# io.net
KiCad netlist of a schematic drawn in Altium Designer
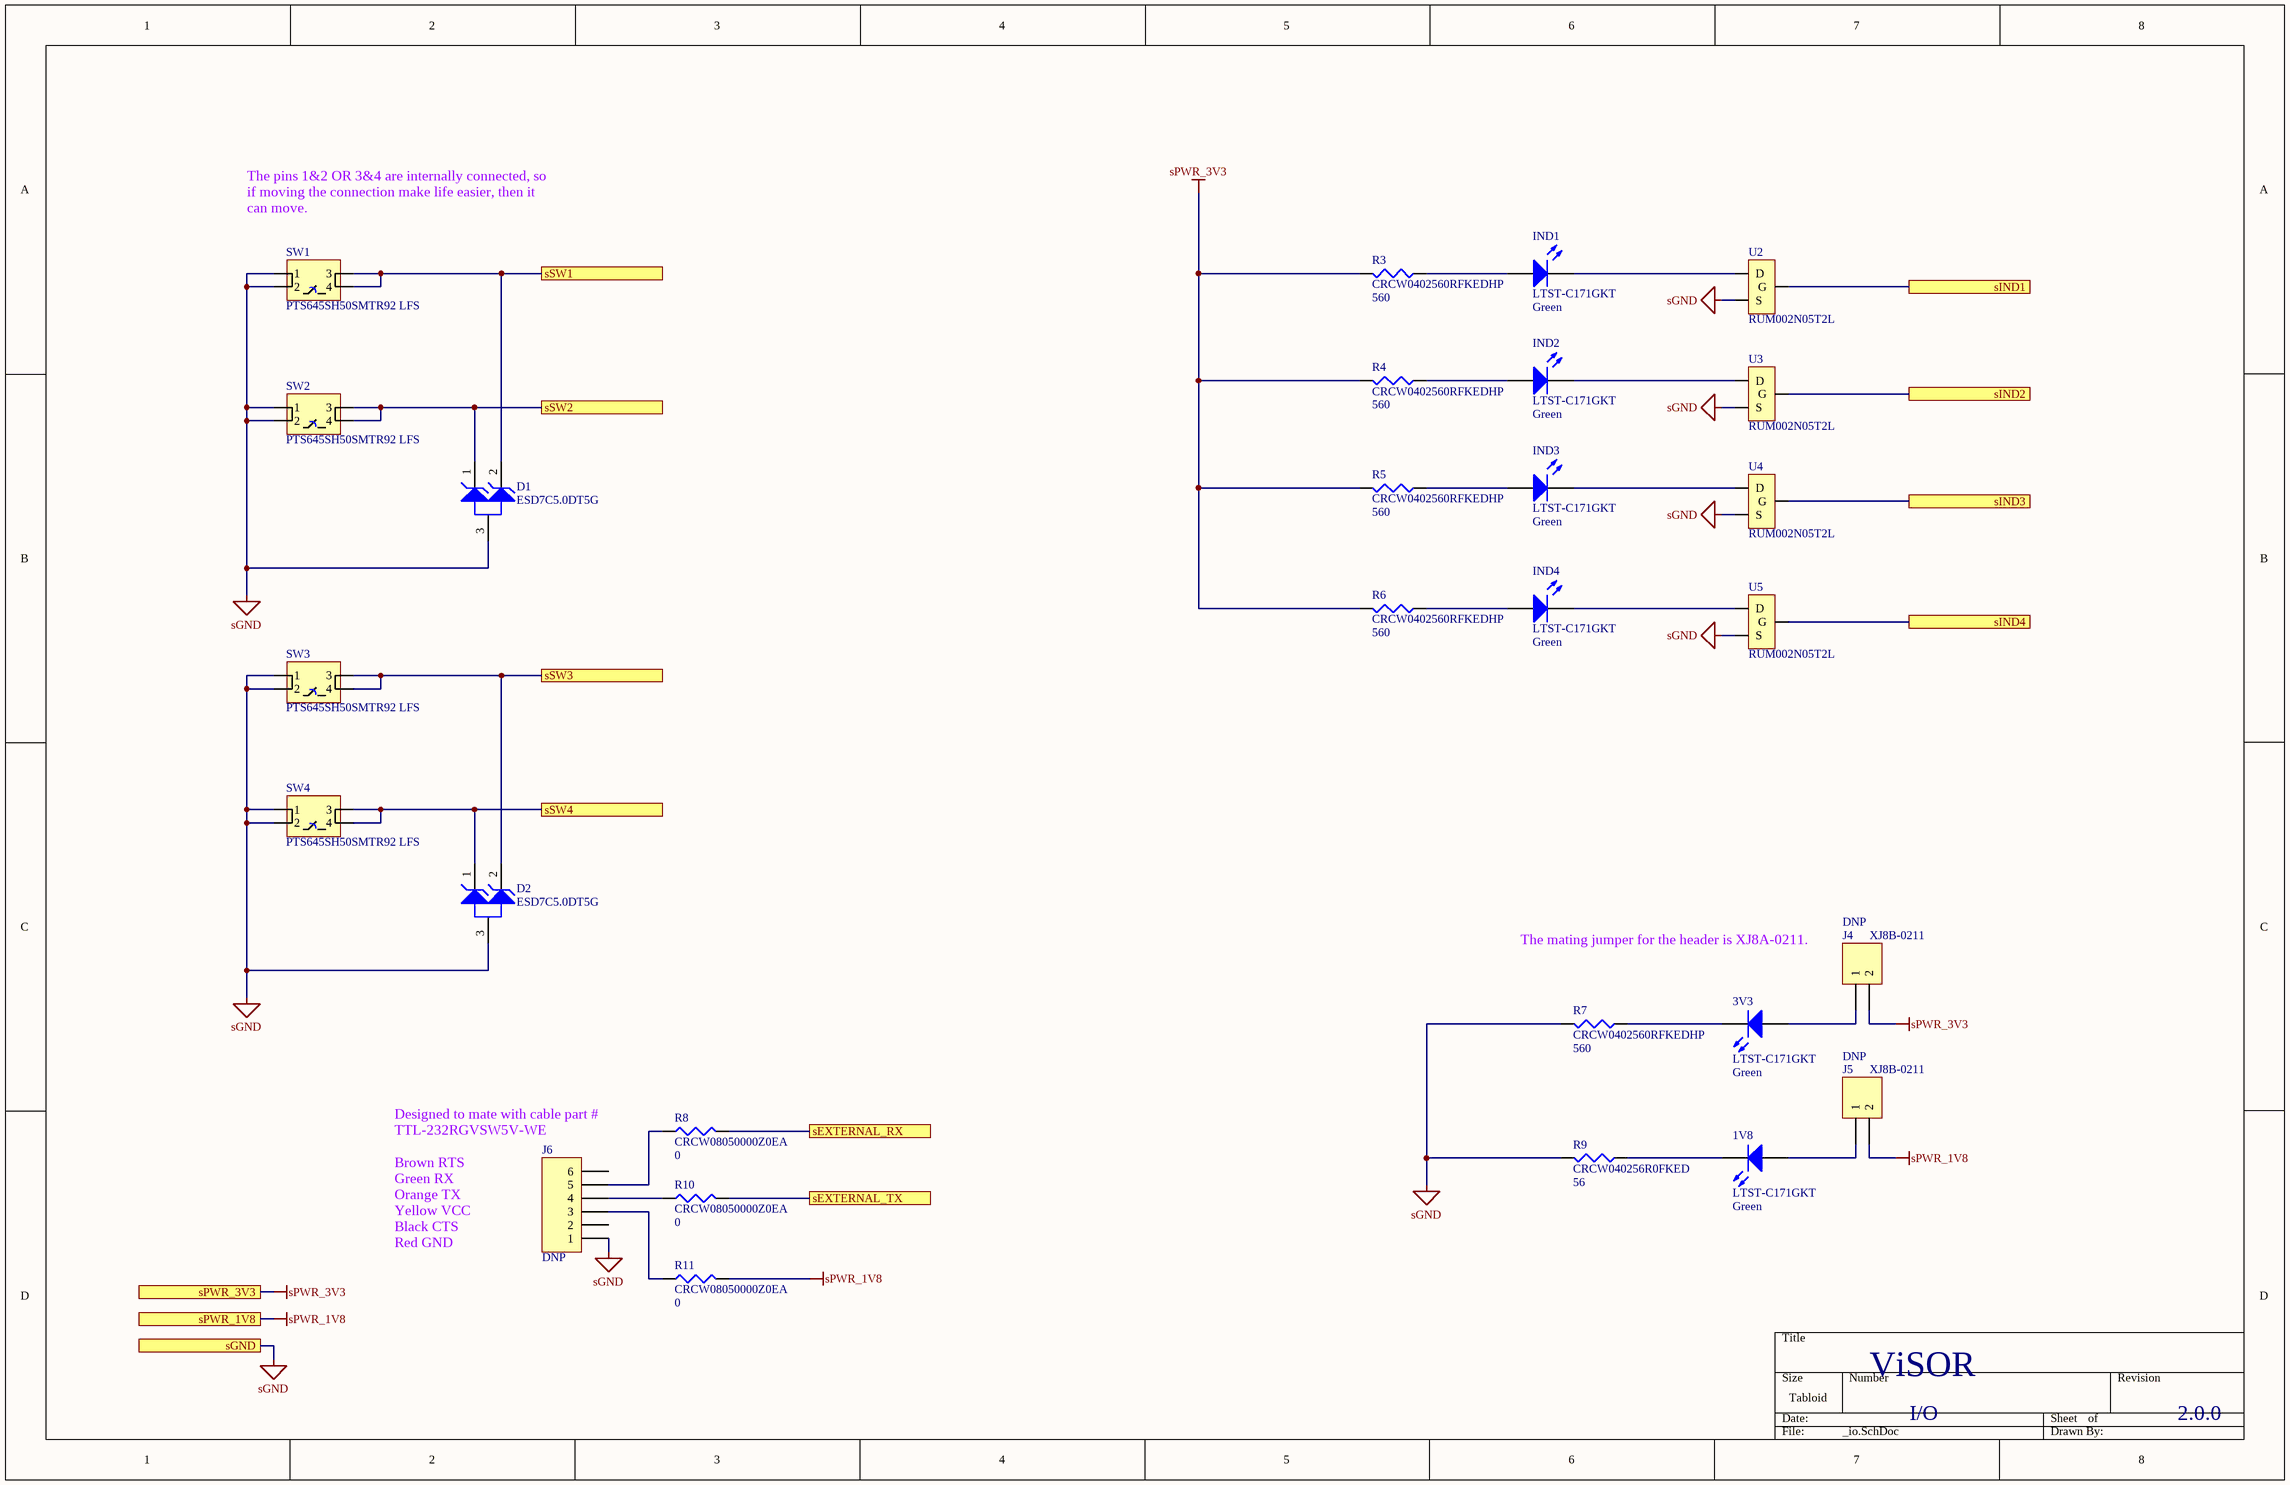
[diagram p0: _io.SchDoc]

(export (version "E")
  (design (tool "Eeschema 10.0.6"))
  (components
    (comp (ref "1V8")
      (value "LTST-C171GKT")
      (footprint "0805")
      (description "LED")
      (fields (field (name "COLOR") "Green"))
      (libsource (lib "lite-on") (part "LTST-C171GKT"))
    )
    (comp (ref "3V3")
      (value "LTST-C171GKT")
      (footprint "0805")
      (description "LED")
      (fields (field (name "COLOR") "Green"))
      (libsource (lib "lite-on") (part "LTST-C171GKT"))
    )
    (comp (ref "D1")
      (value "ESD7C5.0DT5G")
      (footprint "ONSC-SOT-723-3-631AA-01_V")
      (fields (field (name "MANUFACTURER") "On Semiconductor"))
      (libsource (lib "Altium Content Vault") (part "ONSC-K1K2A3-3"))
    )
    (comp (ref "D2")
      (value "ESD7C5.0DT5G")
      (footprint "ONSC-SOT-723-3-631AA-01_V")
      (fields (field (name "MANUFACTURER") "On Semiconductor"))
      (libsource (lib "Altium Content Vault") (part "ONSC-K1K2A3-3"))
    )
    (comp (ref "IND1")
      (value "LTST-C171GKT")
      (footprint "0805")
      (description "LED")
      (fields (field (name "COLOR") "Green"))
      (libsource (lib "lite-on") (part "LTST-C171GKT"))
    )
    (comp (ref "IND2")
      (value "LTST-C171GKT")
      (footprint "0805")
      (description "LED")
      (fields (field (name "COLOR") "Green"))
      (libsource (lib "lite-on") (part "LTST-C171GKT"))
    )
    (comp (ref "IND3")
      (value "LTST-C171GKT")
      (footprint "0805")
      (description "LED")
      (fields (field (name "COLOR") "Green"))
      (libsource (lib "lite-on") (part "LTST-C171GKT"))
    )
    (comp (ref "IND4")
      (value "LTST-C171GKT")
      (footprint "0805")
      (description "LED")
      (fields (field (name "COLOR") "Green"))
      (libsource (lib "lite-on") (part "LTST-C171GKT"))
    )
    (comp (ref "J4")
      (value "XJ8B-0211")
      (footprint "HDR1X2")
      (description "Header, 2-Pin")
      (fields (field (name "DNP") "DNP") (field (name "PUBLISHER") "Altium Limited"))
      (libsource (lib "Miscellaneous Connectors") (part "Header 2"))
    )
    (comp (ref "J5")
      (value "XJ8B-0211")
      (footprint "HDR1X2")
      (description "Header, 2-Pin")
      (fields (field (name "DNP") "DNP") (field (name "PUBLISHER") "Altium Limited"))
      (libsource (lib "Miscellaneous Connectors") (part "Header 2"))
    )
    (comp (ref "J6")
      (value "DNP")
      (footprint "HDR1X6")
      (description "Header, 6-Pin")
      (fields (field (name "PUBLISHER") "Altium Limited"))
      (libsource (lib "miscellaneous_connectors") (part "Header 6"))
    )
    (comp (ref "R3")
      (value "CRCW0402560RFKEDHP")
      (footprint "0402")
      (description "0.125W, -55-155C, 1005, 50V, ±1%")
      (fields (field (name "ALTIUM_VALUE") "560"))
      (libsource (lib "standard_resistors") (part "CRCW0402xxxxFKED"))
    )
    (comp (ref "R4")
      (value "CRCW0402560RFKEDHP")
      (footprint "0402")
      (description "0.125W, -55-155C, 1005, 50V, ±1%")
      (fields (field (name "ALTIUM_VALUE") "560"))
      (libsource (lib "standard_resistors") (part "CRCW0402xxxxFKED"))
    )
    (comp (ref "R5")
      (value "CRCW0402560RFKEDHP")
      (footprint "0402")
      (description "0.125W, -55-155C, 1005, 50V, ±1%")
      (fields (field (name "ALTIUM_VALUE") "560"))
      (libsource (lib "standard_resistors") (part "CRCW0402xxxxFKED"))
    )
    (comp (ref "R6")
      (value "CRCW0402560RFKEDHP")
      (footprint "0402")
      (description "0.125W, -55-155C, 1005, 50V, ±1%")
      (fields (field (name "ALTIUM_VALUE") "560"))
      (libsource (lib "standard_resistors") (part "CRCW0402xxxxFKED"))
    )
    (comp (ref "R7")
      (value "CRCW0402560RFKEDHP")
      (footprint "0402")
      (description "0.125W, -55-155C, 1005, 50V, ±1%")
      (fields (field (name "ALTIUM_VALUE") "560"))
      (libsource (lib "standard_resistors") (part "CRCW0402xxxxFKED"))
    )
    (comp (ref "R8")
      (value "CRCW08050000Z0EA")
      (footprint "6-0805_M")
      (description "0Ω Resistor")
      (fields (field (name "ALTIUM_VALUE") "0") (field (name "PUBLISHER") "Altium Limited"))
      (libsource (lib "miscellaneous_devices") (part "Res3"))
    )
    (comp (ref "R9")
      (value "CRCW040256R0FKED")
      (footprint "0402")
      (description "0.125W, -55-155C, 1005, 50V, ±1%")
      (fields (field (name "ALTIUM_VALUE") "56"))
      (libsource (lib "standard_resistors") (part "CRCW0402xxxxFKED"))
    )
    (comp (ref "R10")
      (value "CRCW08050000Z0EA")
      (footprint "6-0805_M")
      (description "0Ω Resistor")
      (fields (field (name "ALTIUM_VALUE") "0") (field (name "PUBLISHER") "Altium Limited"))
      (libsource (lib "miscellaneous_devices") (part "Res3"))
    )
    (comp (ref "R11")
      (value "CRCW08050000Z0EA")
      (footprint "6-0805_M")
      (description "0Ω Resistor")
      (fields (field (name "ALTIUM_VALUE") "0") (field (name "PUBLISHER") "Altium Limited"))
      (libsource (lib "miscellaneous_devices") (part "Res3"))
    )
    (comp (ref "SW1")
      (value "PTS645SH50SMTR92 LFS")
      (footprint "PTS645SH50SMTR92 LFS")
      (description "Tactile Switch")
      (libsource (lib "candk") (part "PTS645SH50SMTR92 LFS"))
    )
    (comp (ref "SW2")
      (value "PTS645SH50SMTR92 LFS")
      (footprint "PTS645SH50SMTR92 LFS")
      (description "Tactile Switch")
      (libsource (lib "candk") (part "PTS645SH50SMTR92 LFS"))
    )
    (comp (ref "SW3")
      (value "PTS645SH50SMTR92 LFS")
      (footprint "PTS645SH50SMTR92 LFS")
      (description "Tactile Switch")
      (libsource (lib "candk") (part "PTS645SH50SMTR92 LFS"))
    )
    (comp (ref "SW4")
      (value "PTS645SH50SMTR92 LFS")
      (footprint "PTS645SH50SMTR92 LFS")
      (description "Tactile Switch")
      (libsource (lib "candk") (part "PTS645SH50SMTR92 LFS"))
    )
    (comp (ref "U2")
      (value "RUM002N05T2L")
      (footprint "RUM002N05T2L")
      (description "MOSFET N-CH 50V 0.2A 3VMT")
      (libsource (lib "rohm") (part "RUM002N05T2L"))
    )
    (comp (ref "U3")
      (value "RUM002N05T2L")
      (footprint "RUM002N05T2L")
      (description "MOSFET N-CH 50V 0.2A 3VMT")
      (libsource (lib "rohm") (part "RUM002N05T2L"))
    )
    (comp (ref "U4")
      (value "RUM002N05T2L")
      (footprint "RUM002N05T2L")
      (description "MOSFET N-CH 50V 0.2A 3VMT")
      (libsource (lib "rohm") (part "RUM002N05T2L"))
    )
    (comp (ref "U5")
      (value "RUM002N05T2L")
      (footprint "RUM002N05T2L")
      (description "MOSFET N-CH 50V 0.2A 3VMT")
      (libsource (lib "rohm") (part "RUM002N05T2L"))
    )
  )
  (nets
    (net (code "1") (name "/sEXTERNAL_RX") (class "Default")
      (node (ref "R8") (pin "2") (pinfunction "2_2") (pintype "passive"))
    )
    (net (code "2") (name "/sEXTERNAL_TX") (class "Default")
      (node (ref "R10") (pin "2") (pinfunction "2_2") (pintype "passive"))
    )
    (net (code "3") (name "/sIND1") (class "Default")
      (node (ref "U2") (pin "1") (pinfunction "G_1") (pintype "passive"))
    )
    (net (code "4") (name "/sIND2") (class "Default")
      (node (ref "U3") (pin "1") (pinfunction "G_1") (pintype "passive"))
    )
    (net (code "5") (name "/sIND3") (class "Default")
      (node (ref "U4") (pin "1") (pinfunction "G_1") (pintype "passive"))
    )
    (net (code "6") (name "/sIND4") (class "Default")
      (node (ref "U5") (pin "1") (pinfunction "G_1") (pintype "passive"))
    )
    (net (code "7") (name "/sSW1") (class "Default")
      (node (ref "D1") (pin "2") (pinfunction "K2_2") (pintype "passive"))
      (node (ref "SW1") (pin "3") (pinfunction "3_3") (pintype "passive"))
      (node (ref "SW1") (pin "4") (pinfunction "4_4") (pintype "passive"))
    )
    (net (code "8") (name "/sSW2") (class "Default")
      (node (ref "D1") (pin "1") (pinfunction "K1_1") (pintype "passive"))
      (node (ref "SW2") (pin "3") (pinfunction "3_3") (pintype "passive"))
      (node (ref "SW2") (pin "4") (pinfunction "4_4") (pintype "passive"))
    )
    (net (code "9") (name "/sSW3") (class "Default")
      (node (ref "D2") (pin "2") (pinfunction "K2_2") (pintype "passive"))
      (node (ref "SW3") (pin "3") (pinfunction "3_3") (pintype "passive"))
      (node (ref "SW3") (pin "4") (pinfunction "4_4") (pintype "passive"))
    )
    (net (code "10") (name "/sSW4") (class "Default")
      (node (ref "D2") (pin "1") (pinfunction "K1_1") (pintype "passive"))
      (node (ref "SW4") (pin "3") (pinfunction "3_3") (pintype "passive"))
      (node (ref "SW4") (pin "4") (pinfunction "4_4") (pintype "passive"))
    )
    (net (code "11") (name "Net-(1V8-A)") (class "Default")
      (node (ref "1V8") (pin "1") (pinfunction "A_1") (pintype "passive"))
      (node (ref "J5") (pin "1") (pinfunction "1_1") (pintype "passive"))
    )
    (net (code "12") (name "Net-(1V8-K)") (class "Default")
      (node (ref "1V8") (pin "2") (pinfunction "K_2") (pintype "passive"))
      (node (ref "R9") (pin "1") (pinfunction "1_1") (pintype "passive"))
    )
    (net (code "13") (name "Net-(3V3-A)") (class "Default")
      (node (ref "3V3") (pin "1") (pinfunction "A_1") (pintype "passive"))
      (node (ref "J4") (pin "1") (pinfunction "1_1") (pintype "passive"))
    )
    (net (code "14") (name "Net-(3V3-K)") (class "Default")
      (node (ref "3V3") (pin "2") (pinfunction "K_2") (pintype "passive"))
      (node (ref "R7") (pin "1") (pinfunction "1_1") (pintype "passive"))
    )
    (net (code "15") (name "Net-(IND1-A)") (class "Default")
      (node (ref "IND1") (pin "1") (pinfunction "A_1") (pintype "passive"))
      (node (ref "R3") (pin "1") (pinfunction "1_1") (pintype "passive"))
    )
    (net (code "16") (name "Net-(IND1-K)") (class "Default")
      (node (ref "IND1") (pin "2") (pinfunction "K_2") (pintype "passive"))
      (node (ref "U2") (pin "3") (pinfunction "D_3") (pintype "passive"))
    )
    (net (code "17") (name "Net-(IND2-A)") (class "Default")
      (node (ref "IND2") (pin "1") (pinfunction "A_1") (pintype "passive"))
      (node (ref "R4") (pin "1") (pinfunction "1_1") (pintype "passive"))
    )
    (net (code "18") (name "Net-(IND2-K)") (class "Default")
      (node (ref "IND2") (pin "2") (pinfunction "K_2") (pintype "passive"))
      (node (ref "U3") (pin "3") (pinfunction "D_3") (pintype "passive"))
    )
    (net (code "19") (name "Net-(IND3-A)") (class "Default")
      (node (ref "IND3") (pin "1") (pinfunction "A_1") (pintype "passive"))
      (node (ref "R5") (pin "1") (pinfunction "1_1") (pintype "passive"))
    )
    (net (code "20") (name "Net-(IND3-K)") (class "Default")
      (node (ref "IND3") (pin "2") (pinfunction "K_2") (pintype "passive"))
      (node (ref "U4") (pin "3") (pinfunction "D_3") (pintype "passive"))
    )
    (net (code "21") (name "Net-(IND4-A)") (class "Default")
      (node (ref "IND4") (pin "1") (pinfunction "A_1") (pintype "passive"))
      (node (ref "R6") (pin "1") (pinfunction "1_1") (pintype "passive"))
    )
    (net (code "22") (name "Net-(IND4-K)") (class "Default")
      (node (ref "IND4") (pin "2") (pinfunction "K_2") (pintype "passive"))
      (node (ref "U5") (pin "3") (pinfunction "D_3") (pintype "passive"))
    )
    (net (code "23") (name "Net-(J6-Pad3)") (class "Default")
      (node (ref "J6") (pin "3") (pinfunction "3_3") (pintype "passive"))
      (node (ref "R11") (pin "1") (pinfunction "1_1") (pintype "passive"))
    )
    (net (code "24") (name "Net-(J6-Pad4)") (class "Default")
      (node (ref "J6") (pin "4") (pinfunction "4_4") (pintype "passive"))
      (node (ref "R10") (pin "1") (pinfunction "1_1") (pintype "passive"))
    )
    (net (code "25") (name "Net-(J6-Pad5)") (class "Default")
      (node (ref "J6") (pin "5") (pinfunction "5_5") (pintype "passive"))
      (node (ref "R8") (pin "1") (pinfunction "1_1") (pintype "passive"))
    )
    (net (code "26") (name "sGND") (class "Default")
      (node (ref "D1") (pin "3") (pinfunction "A_3") (pintype "passive"))
      (node (ref "D2") (pin "3") (pinfunction "A_3") (pintype "passive"))
      (node (ref "J6") (pin "1") (pinfunction "1_1") (pintype "passive"))
      (node (ref "R7") (pin "2") (pinfunction "2_2") (pintype "passive"))
      (node (ref "R9") (pin "2") (pinfunction "2_2") (pintype "passive"))
      (node (ref "SW1") (pin "1") (pinfunction "1_1") (pintype "passive"))
      (node (ref "SW1") (pin "2") (pinfunction "2_2") (pintype "passive"))
      (node (ref "SW2") (pin "1") (pinfunction "1_1") (pintype "passive"))
      (node (ref "SW2") (pin "2") (pinfunction "2_2") (pintype "passive"))
      (node (ref "SW3") (pin "1") (pinfunction "1_1") (pintype "passive"))
      (node (ref "SW3") (pin "2") (pinfunction "2_2") (pintype "passive"))
      (node (ref "SW4") (pin "1") (pinfunction "1_1") (pintype "passive"))
      (node (ref "SW4") (pin "2") (pinfunction "2_2") (pintype "passive"))
      (node (ref "U2") (pin "2") (pinfunction "S_2") (pintype "passive"))
      (node (ref "U3") (pin "2") (pinfunction "S_2") (pintype "passive"))
      (node (ref "U4") (pin "2") (pinfunction "S_2") (pintype "passive"))
      (node (ref "U5") (pin "2") (pinfunction "S_2") (pintype "passive"))
    )
    (net (code "27") (name "sPWR_1V8") (class "Default")
      (node (ref "J5") (pin "2") (pinfunction "2_2") (pintype "passive"))
      (node (ref "R11") (pin "2") (pinfunction "2_2") (pintype "passive"))
    )
    (net (code "28") (name "sPWR_3V3") (class "Default")
      (node (ref "J4") (pin "2") (pinfunction "2_2") (pintype "passive"))
      (node (ref "R3") (pin "2") (pinfunction "2_2") (pintype "passive"))
      (node (ref "R4") (pin "2") (pinfunction "2_2") (pintype "passive"))
      (node (ref "R5") (pin "2") (pinfunction "2_2") (pintype "passive"))
      (node (ref "R6") (pin "2") (pinfunction "2_2") (pintype "passive"))
    )
    (net (code "29") (name "unconnected-(J6-Pad2)") (class "Default")
      (node (ref "J6") (pin "2") (pinfunction "2_2") (pintype "passive"))
    )
    (net (code "30") (name "unconnected-(J6-Pad6)") (class "Default")
      (node (ref "J6") (pin "6") (pinfunction "6_6") (pintype "passive"))
    )
  )
)
